# Havoc.net
KiCad netlist of a schematic drawn in EAGLE
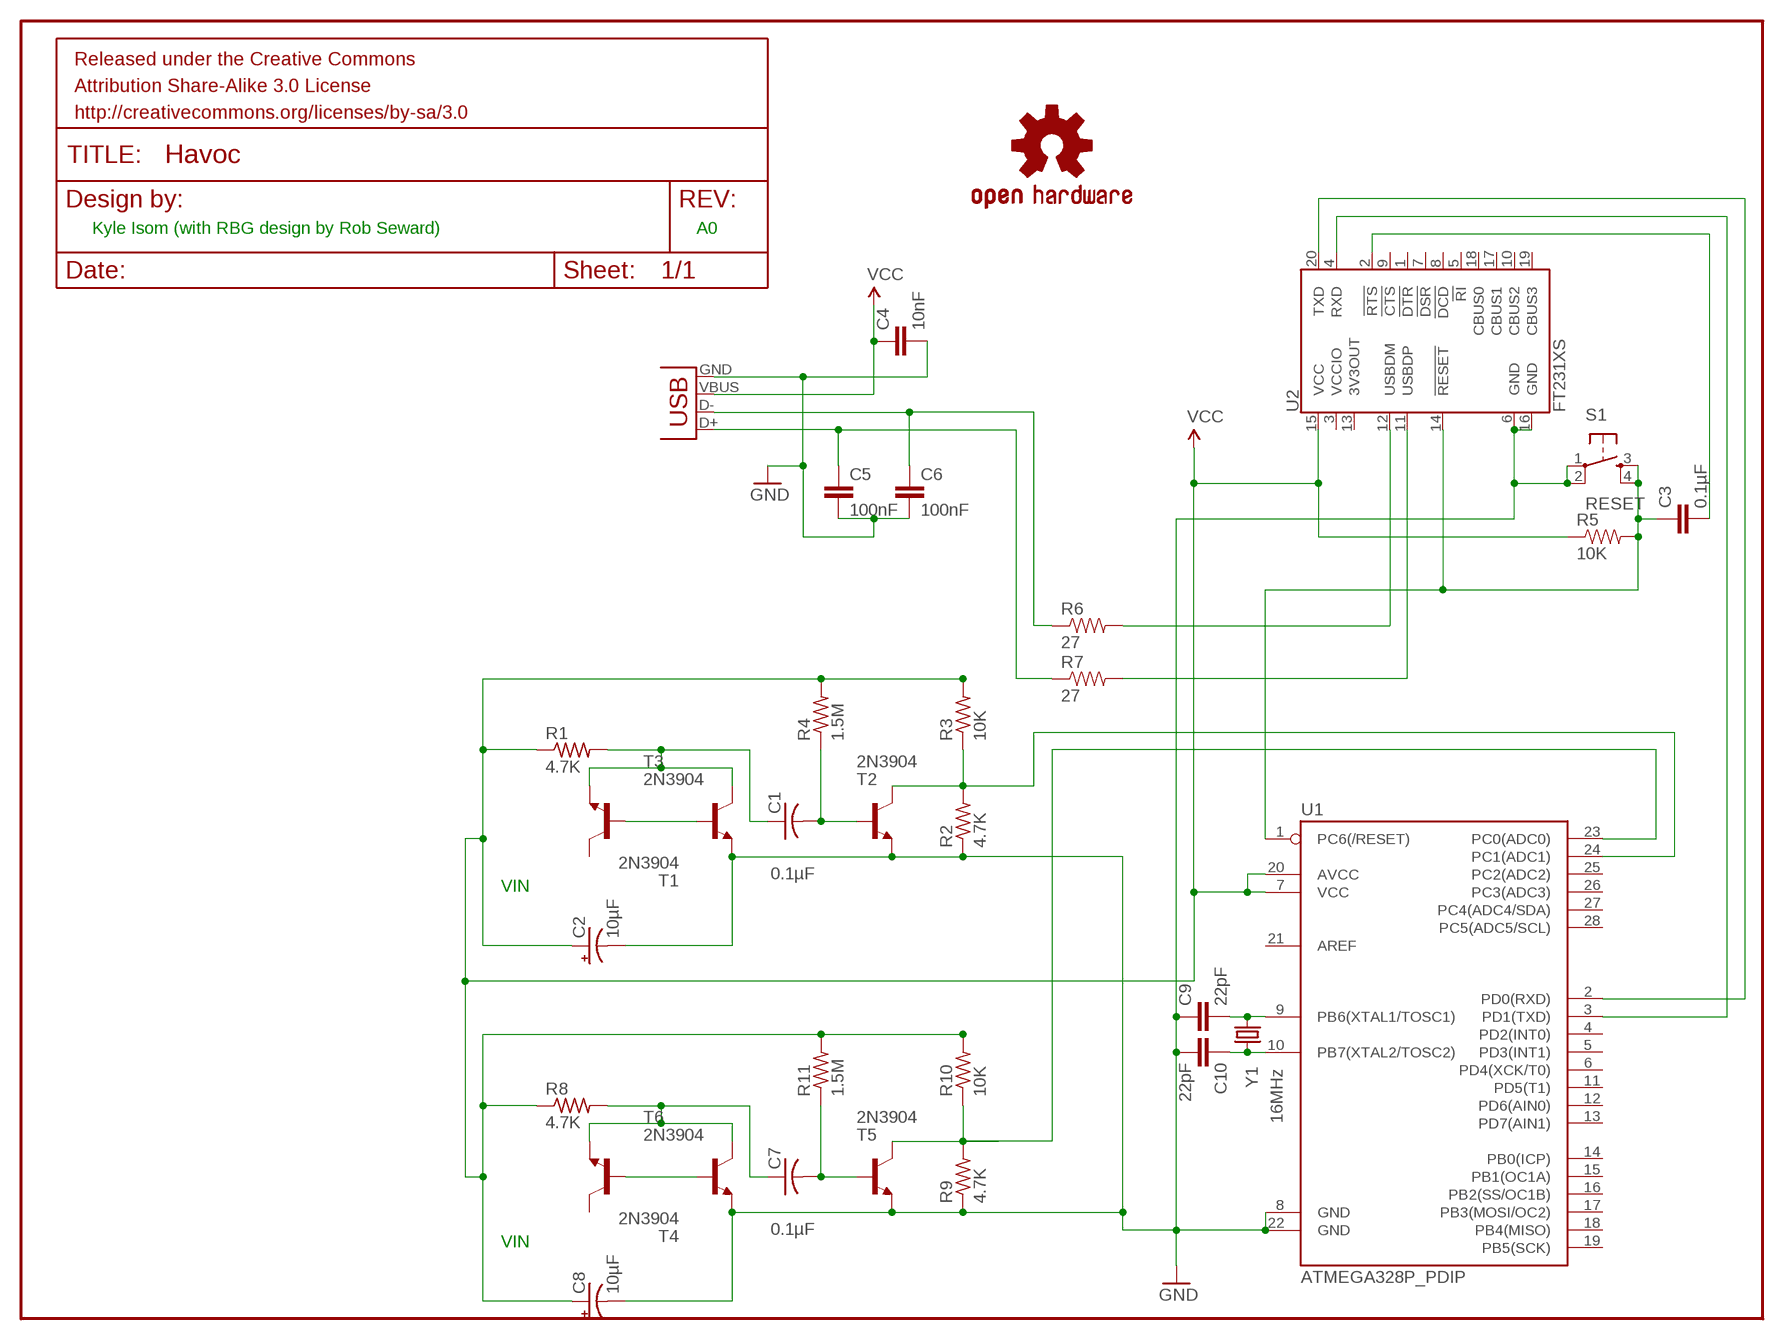
[diagram p0: schematic, sheet 1]

(export (version "E")
  (design (tool "Eeschema 10.0.6"))
  (components
    (comp (ref "C1")
      (value "0.1µF")
      (footprint "eagle-import:C050-030X075")
      (libsource (lib "eagle-import") (part "C-US050-030X075"))
    )
    (comp (ref "C2")
      (value "10µF")
      (footprint "eagle-import:E2-5")
      (libsource (lib "eagle-import") (part "CPOL-USE2-5"))
    )
    (comp (ref "C3")
      (value "0.1µF")
      (footprint "eagle-import:CAP-PTH-SMALL")
      (libsource (lib "eagle-import") (part "SparkFun-Passives_CAPPTH"))
    )
    (comp (ref "C4")
      (value "10nF")
      (footprint "eagle-import:CAP-PTH-SMALL")
      (libsource (lib "eagle-import") (part "SparkFun-Passives_CAPPTH"))
    )
    (comp (ref "C5")
      (value "100nF")
      (footprint "eagle-import:CAP-PTH-SMALL")
      (libsource (lib "eagle-import") (part "CAPPTH"))
    )
    (comp (ref "C6")
      (value "100nF")
      (footprint "eagle-import:CAP-PTH-SMALL")
      (libsource (lib "eagle-import") (part "CAPPTH"))
    )
    (comp (ref "C7")
      (value "0.1µF")
      (footprint "eagle-import:C050-030X075")
      (libsource (lib "eagle-import") (part "C-US050-030X075"))
    )
    (comp (ref "C8")
      (value "10µF")
      (footprint "eagle-import:E2-5")
      (libsource (lib "eagle-import") (part "CPOL-USE2-5"))
    )
    (comp (ref "C9")
      (value "22pF")
      (footprint "eagle-import:CAP-PTH-SMALL")
      (libsource (lib "eagle-import") (part "CAPPTH"))
    )
    (comp (ref "C10")
      (value "22pF")
      (footprint "eagle-import:CAP-PTH-SMALL")
      (libsource (lib "eagle-import") (part "CAPPTH"))
    )
    (comp (ref "FRAME1")
      (value "FRAME-LETTER")
      (footprint "eagle-import:CREATIVE_COMMONS")
      (libsource (lib "eagle-import") (part "FRAME-LETTER"))
    )
    (comp (ref "JP1")
      (value "USBSMD")
      (footprint "eagle-import:USB-MINIB")
      (libsource (lib "eagle-import") (part "USBSMD"))
    )
    (comp (ref "LOGO1")
      (value "OSHW-LOGOM")
      (footprint "eagle-import:OSHW-LOGO-M")
      (libsource (lib "eagle-import") (part "OSHW-LOGOM"))
    )
    (comp (ref "R1")
      (value "4.7K")
      (footprint "eagle-import:0207_7")
      (libsource (lib "eagle-import") (part "R-US_0207/7"))
    )
    (comp (ref "R2")
      (value "4.7K")
      (footprint "eagle-import:0207_7")
      (libsource (lib "eagle-import") (part "R-US_0207/7"))
    )
    (comp (ref "R3")
      (value "10K")
      (footprint "eagle-import:0207_7")
      (libsource (lib "eagle-import") (part "R-US_0207/7"))
    )
    (comp (ref "R4")
      (value "1.5M")
      (footprint "eagle-import:0207_7")
      (libsource (lib "eagle-import") (part "R-US_0207/7"))
    )
    (comp (ref "R5")
      (value "10K")
      (footprint "eagle-import:AXIAL-0.6")
      (libsource (lib "eagle-import") (part "RESISTORPTH-1W"))
    )
    (comp (ref "R6")
      (value "27")
      (footprint "eagle-import:AXIAL-0.6")
      (libsource (lib "eagle-import") (part "RESISTORPTH-1W"))
    )
    (comp (ref "R7")
      (value "27")
      (footprint "eagle-import:AXIAL-0.6")
      (libsource (lib "eagle-import") (part "RESISTORPTH-1W"))
    )
    (comp (ref "R8")
      (value "4.7K")
      (footprint "eagle-import:0207_7")
      (libsource (lib "eagle-import") (part "R-US_0207/7"))
    )
    (comp (ref "R9")
      (value "4.7K")
      (footprint "eagle-import:0207_7")
      (libsource (lib "eagle-import") (part "R-US_0207/7"))
    )
    (comp (ref "R10")
      (value "10K")
      (footprint "eagle-import:0207_7")
      (libsource (lib "eagle-import") (part "R-US_0207/7"))
    )
    (comp (ref "R11")
      (value "1.5M")
      (footprint "eagle-import:0207_7")
      (libsource (lib "eagle-import") (part "R-US_0207/7"))
    )
    (comp (ref "S1")
      (value "RESET")
      (footprint "eagle-import:TACTILE-PTH")
      (libsource (lib "eagle-import") (part "TAC_SWITCHPTH"))
    )
    (comp (ref "T1")
      (value "2N3904")
      (footprint "eagle-import:TO92")
      (libsource (lib "eagle-import") (part "2N3904"))
    )
    (comp (ref "T2")
      (value "2N3904")
      (footprint "eagle-import:TO92")
      (libsource (lib "eagle-import") (part "2N3904"))
    )
    (comp (ref "T3")
      (value "2N3904")
      (footprint "eagle-import:TO92")
      (libsource (lib "eagle-import") (part "2N3904"))
    )
    (comp (ref "T4")
      (value "2N3904")
      (footprint "eagle-import:TO92")
      (libsource (lib "eagle-import") (part "2N3904"))
    )
    (comp (ref "T5")
      (value "2N3904")
      (footprint "eagle-import:TO92")
      (libsource (lib "eagle-import") (part "2N3904"))
    )
    (comp (ref "T6")
      (value "2N3904")
      (footprint "eagle-import:TO92")
      (libsource (lib "eagle-import") (part "2N3904"))
    )
    (comp (ref "U1")
      (value "ATMEGA328P_PDIP")
      (footprint "eagle-import:DIL28-3")
      (libsource (lib "eagle-import") (part "ATMEGA328P_PDIP"))
    )
    (comp (ref "U2")
      (value "FT231XS")
      (footprint "eagle-import:SSOP20_L")
      (libsource (lib "eagle-import") (part "FT231XS"))
    )
    (comp (ref "Y1")
      (value "16MHz")
      (footprint "eagle-import:HC49US")
      (libsource (lib "eagle-import") (part "CRYSTALHC49US"))
    )
  )
  (nets
    (net (code "1") (name "GND") (class "Default")
      (node (ref "C10") (pin "2") (pinfunction "2_2") (pintype "passive"))
      (node (ref "C2") (pin "-") (pinfunction "-_-") (pintype "passive"))
      (node (ref "C4") (pin "2") (pinfunction "2_2") (pintype "passive"))
      (node (ref "C5") (pin "2") (pinfunction "2_2") (pintype "passive"))
      (node (ref "C6") (pin "2") (pinfunction "2_2") (pintype "passive"))
      (node (ref "C8") (pin "-") (pinfunction "-_-") (pintype "passive"))
      (node (ref "C9") (pin "1") (pinfunction "1_1") (pintype "passive"))
      (node (ref "JP1") (pin "GND") (pinfunction "GND_GND") (pintype "bidirectional"))
      (node (ref "R2") (pin "1") (pinfunction "1_1") (pintype "passive"))
      (node (ref "R9") (pin "1") (pinfunction "1_1") (pintype "passive"))
      (node (ref "S1") (pin "1") (pinfunction "1_1") (pintype "passive"))
      (node (ref "S1") (pin "2") (pinfunction "2_2") (pintype "passive"))
      (node (ref "T2") (pin "3") (pinfunction "E_3") (pintype "passive"))
      (node (ref "T3") (pin "3") (pinfunction "E_3") (pintype "passive"))
      (node (ref "T5") (pin "3") (pinfunction "E_3") (pintype "passive"))
      (node (ref "T6") (pin "3") (pinfunction "E_3") (pintype "passive"))
      (node (ref "U1") (pin "22") (pinfunction "GND_22") (pintype "bidirectional"))
      (node (ref "U1") (pin "8") (pinfunction "GND_8") (pintype "bidirectional"))
      (node (ref "U2") (pin "16") (pinfunction "GND_16") (pintype "bidirectional"))
      (node (ref "U2") (pin "6") (pinfunction "GND_6") (pintype "bidirectional"))
    )
    (net (code "2") (name "Net-(R5-2)") (class "Default")
      (node (ref "C3") (pin "1") (pinfunction "1_1") (pintype "passive"))
      (node (ref "R5") (pin "P$2") (pinfunction "2_P$2") (pintype "passive"))
      (node (ref "S1") (pin "3") (pinfunction "3_3") (pintype "passive"))
      (node (ref "S1") (pin "4") (pinfunction "4_4") (pintype "passive"))
      (node (ref "U1") (pin "1") (pinfunction "PC6(/RESET)_1") (pintype "bidirectional"))
      (node (ref "U2") (pin "14") (pinfunction "~{RESET}_14") (pintype "bidirectional"))
    )
    (net (code "3") (name "Net-(R6-1)") (class "Default")
      (node (ref "C6") (pin "1") (pinfunction "1_1") (pintype "passive"))
      (node (ref "JP1") (pin "D-") (pinfunction "D-_D-") (pintype "bidirectional"))
      (node (ref "R6") (pin "P$1") (pinfunction "1_P$1") (pintype "passive"))
    )
    (net (code "4") (name "Net-(R6-2)") (class "Default")
      (node (ref "R6") (pin "P$2") (pinfunction "2_P$2") (pintype "passive"))
      (node (ref "U2") (pin "12") (pinfunction "USBDM_12") (pintype "bidirectional"))
    )
    (net (code "5") (name "Net-(R7-1)") (class "Default")
      (node (ref "C5") (pin "1") (pinfunction "1_1") (pintype "passive"))
      (node (ref "JP1") (pin "D+") (pinfunction "D+_D+") (pintype "bidirectional"))
      (node (ref "R7") (pin "P$1") (pinfunction "1_P$1") (pintype "passive"))
    )
    (net (code "6") (name "Net-(R7-2)") (class "Default")
      (node (ref "R7") (pin "P$2") (pinfunction "2_P$2") (pintype "passive"))
      (node (ref "U2") (pin "11") (pinfunction "USBDP_11") (pintype "bidirectional"))
    )
    (net (code "7") (name "Net-(T1-B)") (class "Default")
      (node (ref "T1") (pin "2") (pinfunction "B_2") (pintype "passive"))
      (node (ref "T3") (pin "2") (pinfunction "B_2") (pintype "passive"))
    )
    (net (code "8") (name "Net-(T1-E)") (class "Default")
      (node (ref "C1") (pin "1") (pinfunction "1_1") (pintype "passive"))
      (node (ref "R1") (pin "2") (pinfunction "2_2") (pintype "passive"))
      (node (ref "T1") (pin "3") (pinfunction "E_3") (pintype "passive"))
      (node (ref "T3") (pin "1") (pinfunction "C_1") (pintype "passive"))
    )
    (net (code "9") (name "Net-(T2-B)") (class "Default")
      (node (ref "C1") (pin "2") (pinfunction "2_2") (pintype "passive"))
      (node (ref "R4") (pin "1") (pinfunction "1_1") (pintype "passive"))
      (node (ref "T2") (pin "2") (pinfunction "B_2") (pintype "passive"))
    )
    (net (code "10") (name "Net-(T2-C)") (class "Default")
      (node (ref "R2") (pin "2") (pinfunction "2_2") (pintype "passive"))
      (node (ref "R3") (pin "1") (pinfunction "1_1") (pintype "passive"))
      (node (ref "T2") (pin "1") (pinfunction "C_1") (pintype "passive"))
      (node (ref "U1") (pin "24") (pinfunction "PC1(ADC1)_24") (pintype "bidirectional"))
    )
    (net (code "11") (name "Net-(T4-B)") (class "Default")
      (node (ref "T4") (pin "2") (pinfunction "B_2") (pintype "passive"))
      (node (ref "T6") (pin "2") (pinfunction "B_2") (pintype "passive"))
    )
    (net (code "12") (name "Net-(T4-E)") (class "Default")
      (node (ref "C7") (pin "1") (pinfunction "1_1") (pintype "passive"))
      (node (ref "R8") (pin "2") (pinfunction "2_2") (pintype "passive"))
      (node (ref "T4") (pin "3") (pinfunction "E_3") (pintype "passive"))
      (node (ref "T6") (pin "1") (pinfunction "C_1") (pintype "passive"))
    )
    (net (code "13") (name "Net-(T5-B)") (class "Default")
      (node (ref "C7") (pin "2") (pinfunction "2_2") (pintype "passive"))
      (node (ref "R11") (pin "1") (pinfunction "1_1") (pintype "passive"))
      (node (ref "T5") (pin "2") (pinfunction "B_2") (pintype "passive"))
    )
    (net (code "14") (name "Net-(T5-C)") (class "Default")
      (node (ref "R10") (pin "1") (pinfunction "1_1") (pintype "passive"))
      (node (ref "R9") (pin "2") (pinfunction "2_2") (pintype "passive"))
      (node (ref "T5") (pin "1") (pinfunction "C_1") (pintype "passive"))
      (node (ref "U1") (pin "23") (pinfunction "PC0(ADC0)_23") (pintype "bidirectional"))
    )
    (net (code "15") (name "Net-(U1-PB6(XTAL1{slash}TOSC1))") (class "Default")
      (node (ref "C9") (pin "2") (pinfunction "2_2") (pintype "passive"))
      (node (ref "U1") (pin "9") (pinfunction "PB6(XTAL1/TOSC1)_9") (pintype "bidirectional"))
      (node (ref "Y1") (pin "2") (pinfunction "2_2") (pintype "passive"))
    )
    (net (code "16") (name "Net-(U1-PB7(XTAL2{slash}TOSC2))") (class "Default")
      (node (ref "C10") (pin "1") (pinfunction "1_1") (pintype "passive"))
      (node (ref "U1") (pin "10") (pinfunction "PB7(XTAL2/TOSC2)_10") (pintype "bidirectional"))
      (node (ref "Y1") (pin "1") (pinfunction "1_1") (pintype "passive"))
    )
    (net (code "17") (name "Net-(U1-PD0(RXD))") (class "Default")
      (node (ref "U1") (pin "2") (pinfunction "PD0(RXD)_2") (pintype "bidirectional"))
      (node (ref "U2") (pin "20") (pinfunction "TXD_20") (pintype "bidirectional"))
    )
    (net (code "18") (name "Net-(U1-PD1(TXD))") (class "Default")
      (node (ref "U1") (pin "3") (pinfunction "PD1(TXD)_3") (pintype "bidirectional"))
      (node (ref "U2") (pin "4") (pinfunction "RXD_4") (pintype "bidirectional"))
    )
    (net (code "19") (name "Net-(U2-~{RTS})") (class "Default")
      (node (ref "C3") (pin "2") (pinfunction "2_2") (pintype "passive"))
      (node (ref "U2") (pin "2") (pinfunction "~{RTS}_2") (pintype "bidirectional"))
    )
    (net (code "20") (name "VCC") (class "Default")
      (node (ref "C2") (pin "+") (pinfunction "+_+") (pintype "passive"))
      (node (ref "C4") (pin "1") (pinfunction "1_1") (pintype "passive"))
      (node (ref "C8") (pin "+") (pinfunction "+_+") (pintype "passive"))
      (node (ref "JP1") (pin "VBUS") (pinfunction "VBUS_VBUS") (pintype "bidirectional"))
      (node (ref "R1") (pin "1") (pinfunction "1_1") (pintype "passive"))
      (node (ref "R10") (pin "2") (pinfunction "2_2") (pintype "passive"))
      (node (ref "R11") (pin "2") (pinfunction "2_2") (pintype "passive"))
      (node (ref "R3") (pin "2") (pinfunction "2_2") (pintype "passive"))
      (node (ref "R4") (pin "2") (pinfunction "2_2") (pintype "passive"))
      (node (ref "R5") (pin "P$1") (pinfunction "1_P$1") (pintype "passive"))
      (node (ref "R8") (pin "1") (pinfunction "1_1") (pintype "passive"))
      (node (ref "U1") (pin "20") (pinfunction "AVCC_20") (pintype "bidirectional"))
      (node (ref "U1") (pin "7") (pinfunction "VCC_7") (pintype "bidirectional"))
      (node (ref "U2") (pin "15") (pinfunction "VCC_15") (pintype "bidirectional"))
    )
    (net (code "21") (name "unconnected-(T1-C-Pad1)") (class "Default")
      (node (ref "T1") (pin "1") (pinfunction "C_1") (pintype "passive"))
    )
    (net (code "22") (name "unconnected-(T4-C-Pad1)") (class "Default")
      (node (ref "T4") (pin "1") (pinfunction "C_1") (pintype "passive"))
    )
    (net (code "23") (name "unconnected-(U1-AREF-Pad21)") (class "Default")
      (node (ref "U1") (pin "21") (pinfunction "AREF_21") (pintype "bidirectional"))
    )
    (net (code "24") (name "unconnected-(U1-PB0(ICP)-Pad14)") (class "Default")
      (node (ref "U1") (pin "14") (pinfunction "PB0(ICP)_14") (pintype "bidirectional"))
    )
    (net (code "25") (name "unconnected-(U1-PB1(OC1A)-Pad15)") (class "Default")
      (node (ref "U1") (pin "15") (pinfunction "PB1(OC1A)_15") (pintype "bidirectional"))
    )
    (net (code "26") (name "unconnected-(U1-PB2(SS{slash}OC1B)-Pad16)") (class "Default")
      (node (ref "U1") (pin "16") (pinfunction "PB2(SS/OC1B)_16") (pintype "bidirectional"))
    )
    (net (code "27") (name "unconnected-(U1-PB3(MOSI{slash}OC2)-Pad17)") (class "Default")
      (node (ref "U1") (pin "17") (pinfunction "PB3(MOSI/OC2)_17") (pintype "bidirectional"))
    )
    (net (code "28") (name "unconnected-(U1-PB4(MISO)-Pad18)") (class "Default")
      (node (ref "U1") (pin "18") (pinfunction "PB4(MISO)_18") (pintype "bidirectional"))
    )
    (net (code "29") (name "unconnected-(U1-PB5(SCK)-Pad19)") (class "Default")
      (node (ref "U1") (pin "19") (pinfunction "PB5(SCK)_19") (pintype "bidirectional"))
    )
    (net (code "30") (name "unconnected-(U1-PC2(ADC2)-Pad25)") (class "Default")
      (node (ref "U1") (pin "25") (pinfunction "PC2(ADC2)_25") (pintype "bidirectional"))
    )
    (net (code "31") (name "unconnected-(U1-PC3(ADC3)-Pad26)") (class "Default")
      (node (ref "U1") (pin "26") (pinfunction "PC3(ADC3)_26") (pintype "bidirectional"))
    )
    (net (code "32") (name "unconnected-(U1-PC4(ADC4{slash}SDA)-Pad27)") (class "Default")
      (node (ref "U1") (pin "27") (pinfunction "PC4(ADC4/SDA)_27") (pintype "bidirectional"))
    )
    (net (code "33") (name "unconnected-(U1-PC5(ADC5{slash}SCL)-Pad28)") (class "Default")
      (node (ref "U1") (pin "28") (pinfunction "PC5(ADC5/SCL)_28") (pintype "bidirectional"))
    )
    (net (code "34") (name "unconnected-(U1-PD2(INT0)-Pad4)") (class "Default")
      (node (ref "U1") (pin "4") (pinfunction "PD2(INT0)_4") (pintype "bidirectional"))
    )
    (net (code "35") (name "unconnected-(U1-PD3(INT1)-Pad5)") (class "Default")
      (node (ref "U1") (pin "5") (pinfunction "PD3(INT1)_5") (pintype "bidirectional"))
    )
    (net (code "36") (name "unconnected-(U1-PD4(XCK{slash}T0)-Pad6)") (class "Default")
      (node (ref "U1") (pin "6") (pinfunction "PD4(XCK/T0)_6") (pintype "bidirectional"))
    )
    (net (code "37") (name "unconnected-(U1-PD5(T1)-Pad11)") (class "Default")
      (node (ref "U1") (pin "11") (pinfunction "PD5(T1)_11") (pintype "bidirectional"))
    )
    (net (code "38") (name "unconnected-(U1-PD6(AIN0)-Pad12)") (class "Default")
      (node (ref "U1") (pin "12") (pinfunction "PD6(AIN0)_12") (pintype "bidirectional"))
    )
    (net (code "39") (name "unconnected-(U1-PD7(AIN1)-Pad13)") (class "Default")
      (node (ref "U1") (pin "13") (pinfunction "PD7(AIN1)_13") (pintype "bidirectional"))
    )
    (net (code "40") (name "unconnected-(U2-3V3OUT-Pad13)") (class "Default")
      (node (ref "U2") (pin "13") (pinfunction "3V3OUT_13") (pintype "bidirectional"))
    )
    (net (code "41") (name "unconnected-(U2-CBUS0-Pad18)") (class "Default")
      (node (ref "U2") (pin "18") (pinfunction "CBUS0_18") (pintype "bidirectional"))
    )
    (net (code "42") (name "unconnected-(U2-CBUS1-Pad17)") (class "Default")
      (node (ref "U2") (pin "17") (pinfunction "CBUS1_17") (pintype "bidirectional"))
    )
    (net (code "43") (name "unconnected-(U2-CBUS2-Pad10)") (class "Default")
      (node (ref "U2") (pin "10") (pinfunction "CBUS2_10") (pintype "bidirectional"))
    )
    (net (code "44") (name "unconnected-(U2-CBUS3-Pad19)") (class "Default")
      (node (ref "U2") (pin "19") (pinfunction "CBUS3_19") (pintype "bidirectional"))
    )
    (net (code "45") (name "unconnected-(U2-VCCIO-Pad3)") (class "Default")
      (node (ref "U2") (pin "3") (pinfunction "VCCIO_3") (pintype "bidirectional"))
    )
    (net (code "46") (name "unconnected-(U2-~{CTS}-Pad9)") (class "Default")
      (node (ref "U2") (pin "9") (pinfunction "~{CTS}_9") (pintype "bidirectional"))
    )
    (net (code "47") (name "unconnected-(U2-~{DCD}-Pad8)") (class "Default")
      (node (ref "U2") (pin "8") (pinfunction "~{DCD}_8") (pintype "bidirectional"))
    )
    (net (code "48") (name "unconnected-(U2-~{DSR}-Pad7)") (class "Default")
      (node (ref "U2") (pin "7") (pinfunction "~{DSR}_7") (pintype "bidirectional"))
    )
    (net (code "49") (name "unconnected-(U2-~{DTR}-Pad1)") (class "Default")
      (node (ref "U2") (pin "1") (pinfunction "~{DTR}_1") (pintype "bidirectional"))
    )
    (net (code "50") (name "unconnected-(U2-~{RI}-Pad5)") (class "Default")
      (node (ref "U2") (pin "5") (pinfunction "~{RI}_5") (pintype "bidirectional"))
    )
  )
)
